# SpectroSlave.net
KiCad netlist of a schematic drawn in EAGLE
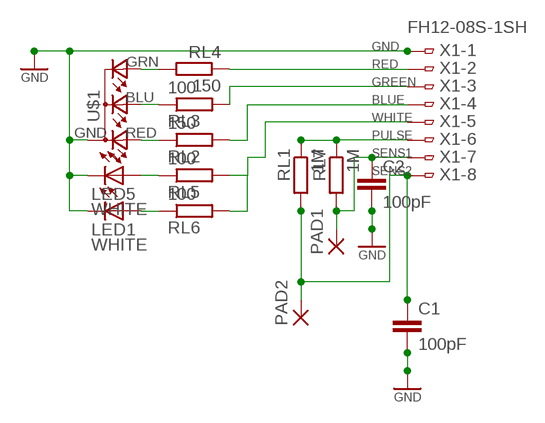
[diagram p0: schematic, sheet 1]

(export (version "E")
  (design (tool "Eeschema 10.0.6"))
  (components
    (comp (ref "C1")
      (value "100pF")
      (footprint "eagle-import:C0805")
      (libsource (lib "eagle-import") (part "C-EUC0805"))
    )
    (comp (ref "C2")
      (value "100pF")
      (footprint "eagle-import:C0805")
      (libsource (lib "eagle-import") (part "C-EUC0805"))
    )
    (comp (ref "LED1")
      (value "WHITE")
      (footprint "eagle-import:CHIP-LED0805")
      (libsource (lib "eagle-import") (part "LEDCHIP-LED0805"))
    )
    (comp (ref "LED5")
      (value "WHITE")
      (footprint "eagle-import:CHIP-LED0805")
      (libsource (lib "eagle-import") (part "LEDCHIP-LED0805"))
    )
    (comp (ref "PAD1")
      (value "SMD5")
      (footprint "eagle-import:SMD2,54-5,08")
      (libsource (lib "eagle-import") (part "SMD5"))
    )
    (comp (ref "PAD2")
      (value "SMD5")
      (footprint "eagle-import:SMD2,54-5,08")
      (libsource (lib "eagle-import") (part "SMD5"))
    )
    (comp (ref "RL1")
      (value "1M")
      (footprint "eagle-import:R0805")
      (libsource (lib "eagle-import") (part "R-EU_R0805"))
    )
    (comp (ref "RL2")
      (value "150")
      (footprint "eagle-import:R0805")
      (libsource (lib "eagle-import") (part "R-EU_R0805"))
    )
    (comp (ref "RL3")
      (value "100")
      (footprint "eagle-import:R0805")
      (libsource (lib "eagle-import") (part "R-EU_R0805"))
    )
    (comp (ref "RL4")
      (value "150")
      (footprint "eagle-import:R0805")
      (libsource (lib "eagle-import") (part "R-EU_R0805"))
    )
    (comp (ref "RL5")
      (value "100")
      (footprint "eagle-import:R0805")
      (libsource (lib "eagle-import") (part "R-EU_R0805"))
    )
    (comp (ref "RL6")
      (value "100")
      (footprint "eagle-import:R0805")
      (libsource (lib "eagle-import") (part "R-EU_R0805"))
    )
    (comp (ref "RL7")
      (value "1M")
      (footprint "eagle-import:R0805")
      (libsource (lib "eagle-import") (part "R-EU_R0805"))
    )
    (comp (ref "U$1")
      (value "RGB-COMMON-CATHODE")
      (footprint "eagle-import:LED-TRICOLOR-THROUGHHOLE")
      (libsource (lib "eagle-import") (part "RGB-COMMON-CATHODE"))
    )
    (comp (ref "X1")
      (value "FH12-08S-1SH")
      (footprint "eagle-import:FH12-08S-1SH")
      (libsource (lib "eagle-import") (part "FH12-08S-1SH"))
    )
  )
  (nets
    (net (code "1") (name "/BLUE") (class "Default")
      (node (ref "RL2") (pin "2") (pinfunction "2_2") (pintype "passive"))
      (node (ref "X1") (pin "4") (pinfunction "1_4") (pintype "passive"))
    )
    (net (code "2") (name "/GREEN") (class "Default")
      (node (ref "RL3") (pin "2") (pinfunction "2_2") (pintype "passive"))
      (node (ref "X1") (pin "3") (pinfunction "1_3") (pintype "passive"))
    )
    (net (code "3") (name "/PULSE") (class "Default")
      (node (ref "RL1") (pin "1") (pinfunction "1_1") (pintype "passive"))
      (node (ref "RL7") (pin "1") (pinfunction "1_1") (pintype "passive"))
      (node (ref "X1") (pin "6") (pinfunction "1_6") (pintype "passive"))
    )
    (net (code "4") (name "/RED") (class "Default")
      (node (ref "RL4") (pin "1") (pinfunction "1_1") (pintype "passive"))
      (node (ref "X1") (pin "2") (pinfunction "1_2") (pintype "passive"))
    )
    (net (code "5") (name "/SENS1") (class "Default")
      (node (ref "C2") (pin "1") (pinfunction "1_1") (pintype "passive"))
      (node (ref "PAD1") (pin "1") (pinfunction "P_1") (pintype "passive"))
      (node (ref "RL7") (pin "2") (pinfunction "2_2") (pintype "passive"))
      (node (ref "X1") (pin "7") (pinfunction "1_7") (pintype "passive"))
    )
    (net (code "6") (name "/SENS2") (class "Default")
      (node (ref "C1") (pin "1") (pinfunction "1_1") (pintype "passive"))
      (node (ref "PAD2") (pin "1") (pinfunction "P_1") (pintype "passive"))
      (node (ref "RL1") (pin "2") (pinfunction "2_2") (pintype "passive"))
      (node (ref "X1") (pin "8") (pinfunction "1_8") (pintype "passive"))
    )
    (net (code "7") (name "/WHITE") (class "Default")
      (node (ref "RL5") (pin "2") (pinfunction "2_2") (pintype "passive"))
      (node (ref "RL6") (pin "2") (pinfunction "2_2") (pintype "passive"))
      (node (ref "X1") (pin "5") (pinfunction "1_5") (pintype "passive"))
    )
    (net (code "8") (name "GND") (class "Default")
      (node (ref "C1") (pin "2") (pinfunction "2_2") (pintype "passive"))
      (node (ref "C2") (pin "2") (pinfunction "2_2") (pintype "passive"))
      (node (ref "LED1") (pin "C") (pinfunction "C_C") (pintype "passive"))
      (node (ref "LED5") (pin "C") (pinfunction "C_C") (pintype "passive"))
      (node (ref "U$1") (pin "GND") (pinfunction "A2_GND") (pintype "passive"))
      (node (ref "X1") (pin "1") (pinfunction "1_1") (pintype "passive"))
    )
    (net (code "9") (name "Net-(LED1-PadA)") (class "Default")
      (node (ref "LED1") (pin "A") (pinfunction "A_A") (pintype "passive"))
      (node (ref "RL6") (pin "1") (pinfunction "1_1") (pintype "passive"))
    )
    (net (code "10") (name "Net-(LED5-PadA)") (class "Default")
      (node (ref "LED5") (pin "A") (pinfunction "A_A") (pintype "passive"))
      (node (ref "RL5") (pin "1") (pinfunction "1_1") (pintype "passive"))
    )
    (net (code "11") (name "Net-(U$1-CBLUE)") (class "Default")
      (node (ref "RL3") (pin "1") (pinfunction "1_1") (pintype "passive"))
      (node (ref "U$1") (pin "BLU") (pinfunction "CBLUE_BLU") (pintype "passive"))
    )
    (net (code "12") (name "Net-(U$1-CGREEN)") (class "Default")
      (node (ref "RL4") (pin "2") (pinfunction "2_2") (pintype "passive"))
      (node (ref "U$1") (pin "GRN") (pinfunction "CGREEN_GRN") (pintype "passive"))
    )
    (net (code "13") (name "Net-(U$1-CRED)") (class "Default")
      (node (ref "RL2") (pin "1") (pinfunction "1_1") (pintype "passive"))
      (node (ref "U$1") (pin "RED") (pinfunction "CRED_RED") (pintype "passive"))
    )
  )
)
